# FilamentRecyclePeriphery.net
KiCad netlist of a schematic drawn in EAGLE
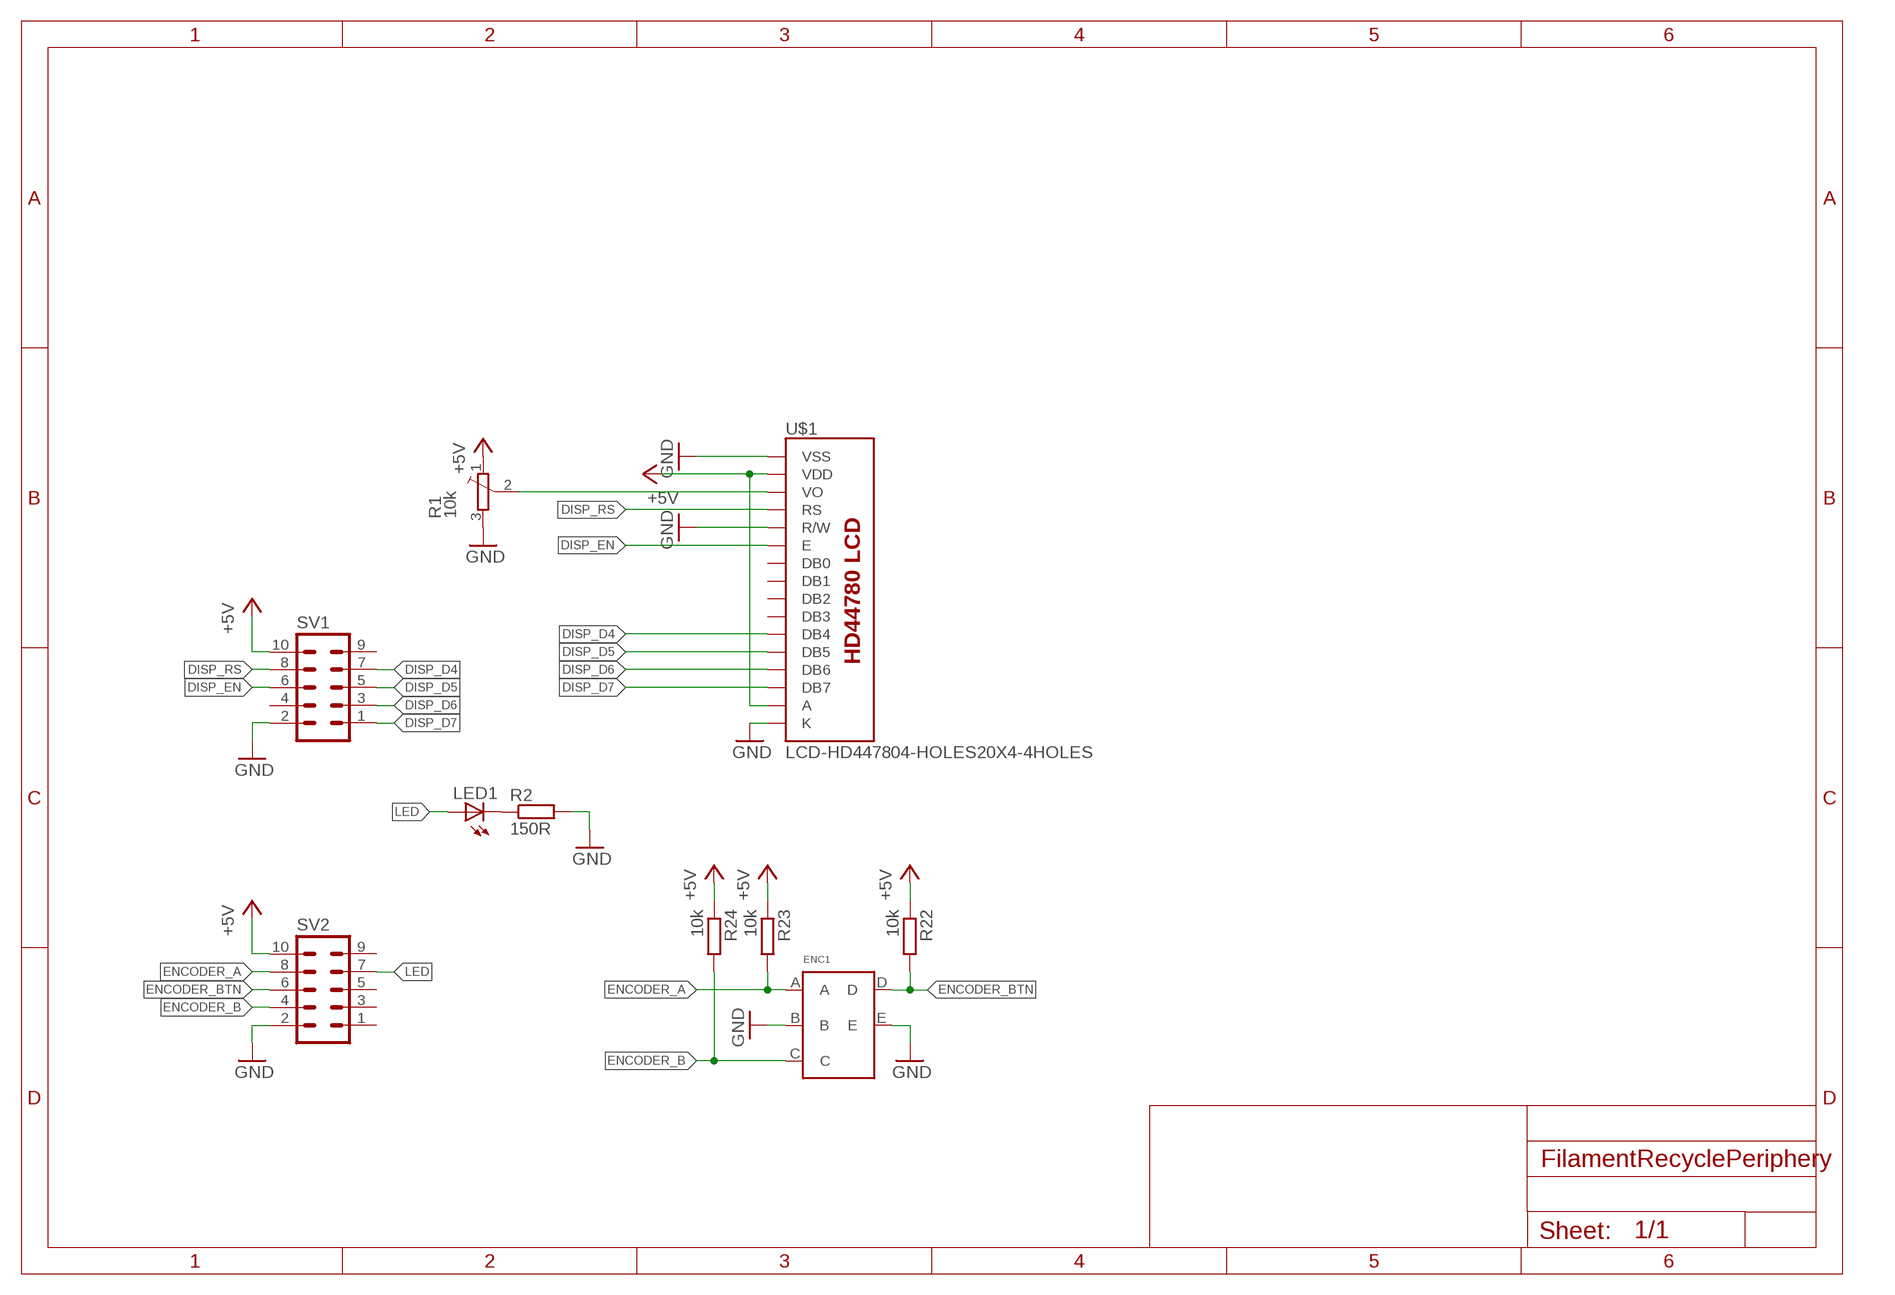
[diagram p0: schematic, sheet 1]

(export (version "E")
  (design (tool "Eeschema 10.0.6"))
  (components
    (comp (ref "ENC1")
      (value "ENCODER")
      (footprint "eagle-import:ENCODER")
      (libsource (lib "eagle-import") (part "ENCODER"))
    )
    (comp (ref "LED1")
      (value "LED3MM")
      (footprint "eagle-import:LED3MM")
      (libsource (lib "eagle-import") (part "LED3MM"))
    )
    (comp (ref "R1")
      (value "10k")
      (footprint "eagle-import:35WR5KLFTR")
      (libsource (lib "eagle-import") (part "35WR5KLFTR"))
    )
    (comp (ref "R2")
      (value "150R")
      (footprint "eagle-import:R0603")
      (libsource (lib "eagle-import") (part "R-EU_R0603"))
    )
    (comp (ref "R22")
      (value "10k")
      (footprint "eagle-import:R0603")
      (libsource (lib "eagle-import") (part "R-EU_R0603"))
    )
    (comp (ref "R23")
      (value "10k")
      (footprint "eagle-import:R0603")
      (libsource (lib "eagle-import") (part "R-EU_R0603"))
    )
    (comp (ref "R24")
      (value "10k")
      (footprint "eagle-import:R0603")
      (libsource (lib "eagle-import") (part "R-EU_R0603"))
    )
    (comp (ref "SV1")
      (value "ML10")
      (footprint "eagle-import:ML10")
      (libsource (lib "eagle-import") (part "ML10"))
    )
    (comp (ref "SV2")
      (value "ML10")
      (footprint "eagle-import:ML10")
      (libsource (lib "eagle-import") (part "ML10"))
    )
    (comp (ref "U$1")
      (value "LCD-HD447804-HOLES20X4-4HOLES")
      (footprint "eagle-import:LCD-20X4-4HOLES")
      (libsource (lib "eagle-import") (part "LCD-HD4478020X4-4HOLES4-HOLES"))
    )
  )
  (nets
    (net (code "1") (name "+5V") (class "Default")
      (node (ref "R1") (pin "1") (pinfunction "E_1") (pintype "passive"))
      (node (ref "R22") (pin "1") (pinfunction "1_1") (pintype "passive"))
      (node (ref "R23") (pin "1") (pinfunction "1_1") (pintype "passive"))
      (node (ref "R24") (pin "1") (pinfunction "1_1") (pintype "passive"))
      (node (ref "SV1") (pin "10") (pinfunction "10_10") (pintype "passive"))
      (node (ref "SV2") (pin "10") (pinfunction "10_10") (pintype "passive"))
      (node (ref "U$1") (pin "P$15") (pinfunction "A_P$15") (pintype "power_in"))
      (node (ref "U$1") (pin "P$2") (pinfunction "VDD_P$2") (pintype "power_in"))
    )
    (net (code "2") (name "DISP_D4") (class "Default")
      (node (ref "SV1") (pin "7") (pinfunction "7_7") (pintype "passive"))
      (node (ref "U$1") (pin "P$11") (pinfunction "DB4_P$11") (pintype "bidirectional"))
    )
    (net (code "3") (name "DISP_D5") (class "Default")
      (node (ref "SV1") (pin "5") (pinfunction "5_5") (pintype "passive"))
      (node (ref "U$1") (pin "P$12") (pinfunction "DB5_P$12") (pintype "bidirectional"))
    )
    (net (code "4") (name "DISP_D6") (class "Default")
      (node (ref "SV1") (pin "3") (pinfunction "3_3") (pintype "passive"))
      (node (ref "U$1") (pin "P$13") (pinfunction "DB6_P$13") (pintype "bidirectional"))
    )
    (net (code "5") (name "DISP_D7") (class "Default")
      (node (ref "SV1") (pin "1") (pinfunction "1_1") (pintype "passive"))
      (node (ref "U$1") (pin "P$14") (pinfunction "DB7_P$14") (pintype "bidirectional"))
    )
    (net (code "6") (name "DISP_EN") (class "Default")
      (node (ref "SV1") (pin "6") (pinfunction "6_6") (pintype "passive"))
      (node (ref "U$1") (pin "P$6") (pinfunction "E_P$6") (pintype "input"))
    )
    (net (code "7") (name "DISP_RS") (class "Default")
      (node (ref "SV1") (pin "8") (pinfunction "8_8") (pintype "passive"))
      (node (ref "U$1") (pin "P$4") (pinfunction "RS_P$4") (pintype "input"))
    )
    (net (code "8") (name "ENCODER_A") (class "Default")
      (node (ref "ENC1") (pin "A") (pinfunction "A_A") (pintype "output"))
      (node (ref "R23") (pin "2") (pinfunction "2_2") (pintype "passive"))
      (node (ref "SV2") (pin "8") (pinfunction "8_8") (pintype "passive"))
    )
    (net (code "9") (name "ENCODER_B") (class "Default")
      (node (ref "ENC1") (pin "C") (pinfunction "C_C") (pintype "power_in"))
      (node (ref "R24") (pin "2") (pinfunction "2_2") (pintype "passive"))
      (node (ref "SV2") (pin "4") (pinfunction "4_4") (pintype "passive"))
    )
    (net (code "10") (name "ENCODER_BTN") (class "Default")
      (node (ref "ENC1") (pin "D") (pinfunction "D_D") (pintype "output"))
      (node (ref "R22") (pin "2") (pinfunction "2_2") (pintype "passive"))
      (node (ref "SV2") (pin "6") (pinfunction "6_6") (pintype "passive"))
    )
    (net (code "11") (name "GND") (class "Default")
      (node (ref "ENC1") (pin "B") (pinfunction "B_B") (pintype "output"))
      (node (ref "ENC1") (pin "E") (pinfunction "E_E") (pintype "power_in"))
      (node (ref "R1") (pin "3") (pinfunction "A_3") (pintype "passive"))
      (node (ref "R2") (pin "2") (pinfunction "2_2") (pintype "passive"))
      (node (ref "SV1") (pin "2") (pinfunction "2_2") (pintype "passive"))
      (node (ref "SV2") (pin "2") (pinfunction "2_2") (pintype "passive"))
      (node (ref "U$1") (pin "P$1") (pinfunction "VSS_P$1") (pintype "power_in"))
      (node (ref "U$1") (pin "P$16") (pinfunction "K_P$16") (pintype "power_in"))
      (node (ref "U$1") (pin "P$5") (pinfunction "R/W_P$5") (pintype "input"))
    )
    (net (code "12") (name "LED") (class "Default")
      (node (ref "LED1") (pin "A") (pinfunction "A_A") (pintype "passive"))
      (node (ref "SV2") (pin "7") (pinfunction "7_7") (pintype "passive"))
    )
    (net (code "13") (name "Net-(LED1-C)") (class "Default")
      (node (ref "LED1") (pin "K") (pinfunction "C_K") (pintype "passive"))
      (node (ref "R2") (pin "1") (pinfunction "1_1") (pintype "passive"))
    )
    (net (code "14") (name "Net-(R1-S)") (class "Default")
      (node (ref "R1") (pin "2") (pinfunction "S_2") (pintype "passive"))
      (node (ref "U$1") (pin "P$3") (pinfunction "VO_P$3") (pintype "bidirectional"))
    )
    (net (code "15") (name "unconnected-(SV1-Pad4)") (class "Default")
      (node (ref "SV1") (pin "4") (pinfunction "4_4") (pintype "passive"))
    )
    (net (code "16") (name "unconnected-(SV1-Pad9)") (class "Default")
      (node (ref "SV1") (pin "9") (pinfunction "9_9") (pintype "passive"))
    )
    (net (code "17") (name "unconnected-(SV2-Pad1)") (class "Default")
      (node (ref "SV2") (pin "1") (pinfunction "1_1") (pintype "passive"))
    )
    (net (code "18") (name "unconnected-(SV2-Pad3)") (class "Default")
      (node (ref "SV2") (pin "3") (pinfunction "3_3") (pintype "passive"))
    )
    (net (code "19") (name "unconnected-(SV2-Pad5)") (class "Default")
      (node (ref "SV2") (pin "5") (pinfunction "5_5") (pintype "passive"))
    )
    (net (code "20") (name "unconnected-(SV2-Pad9)") (class "Default")
      (node (ref "SV2") (pin "9") (pinfunction "9_9") (pintype "passive"))
    )
    (net (code "21") (name "unconnected-(U$1-DB0-PadP$7)") (class "Default")
      (node (ref "U$1") (pin "P$7") (pinfunction "DB0_P$7") (pintype "bidirectional"))
    )
    (net (code "22") (name "unconnected-(U$1-DB1-PadP$8)") (class "Default")
      (node (ref "U$1") (pin "P$8") (pinfunction "DB1_P$8") (pintype "bidirectional"))
    )
    (net (code "23") (name "unconnected-(U$1-DB2-PadP$9)") (class "Default")
      (node (ref "U$1") (pin "P$9") (pinfunction "DB2_P$9") (pintype "bidirectional"))
    )
    (net (code "24") (name "unconnected-(U$1-DB3-PadP$10)") (class "Default")
      (node (ref "U$1") (pin "P$10") (pinfunction "DB3_P$10") (pintype "bidirectional"))
    )
  )
)
